# Receiver.net
KiCad netlist of a schematic drawn in EAGLE
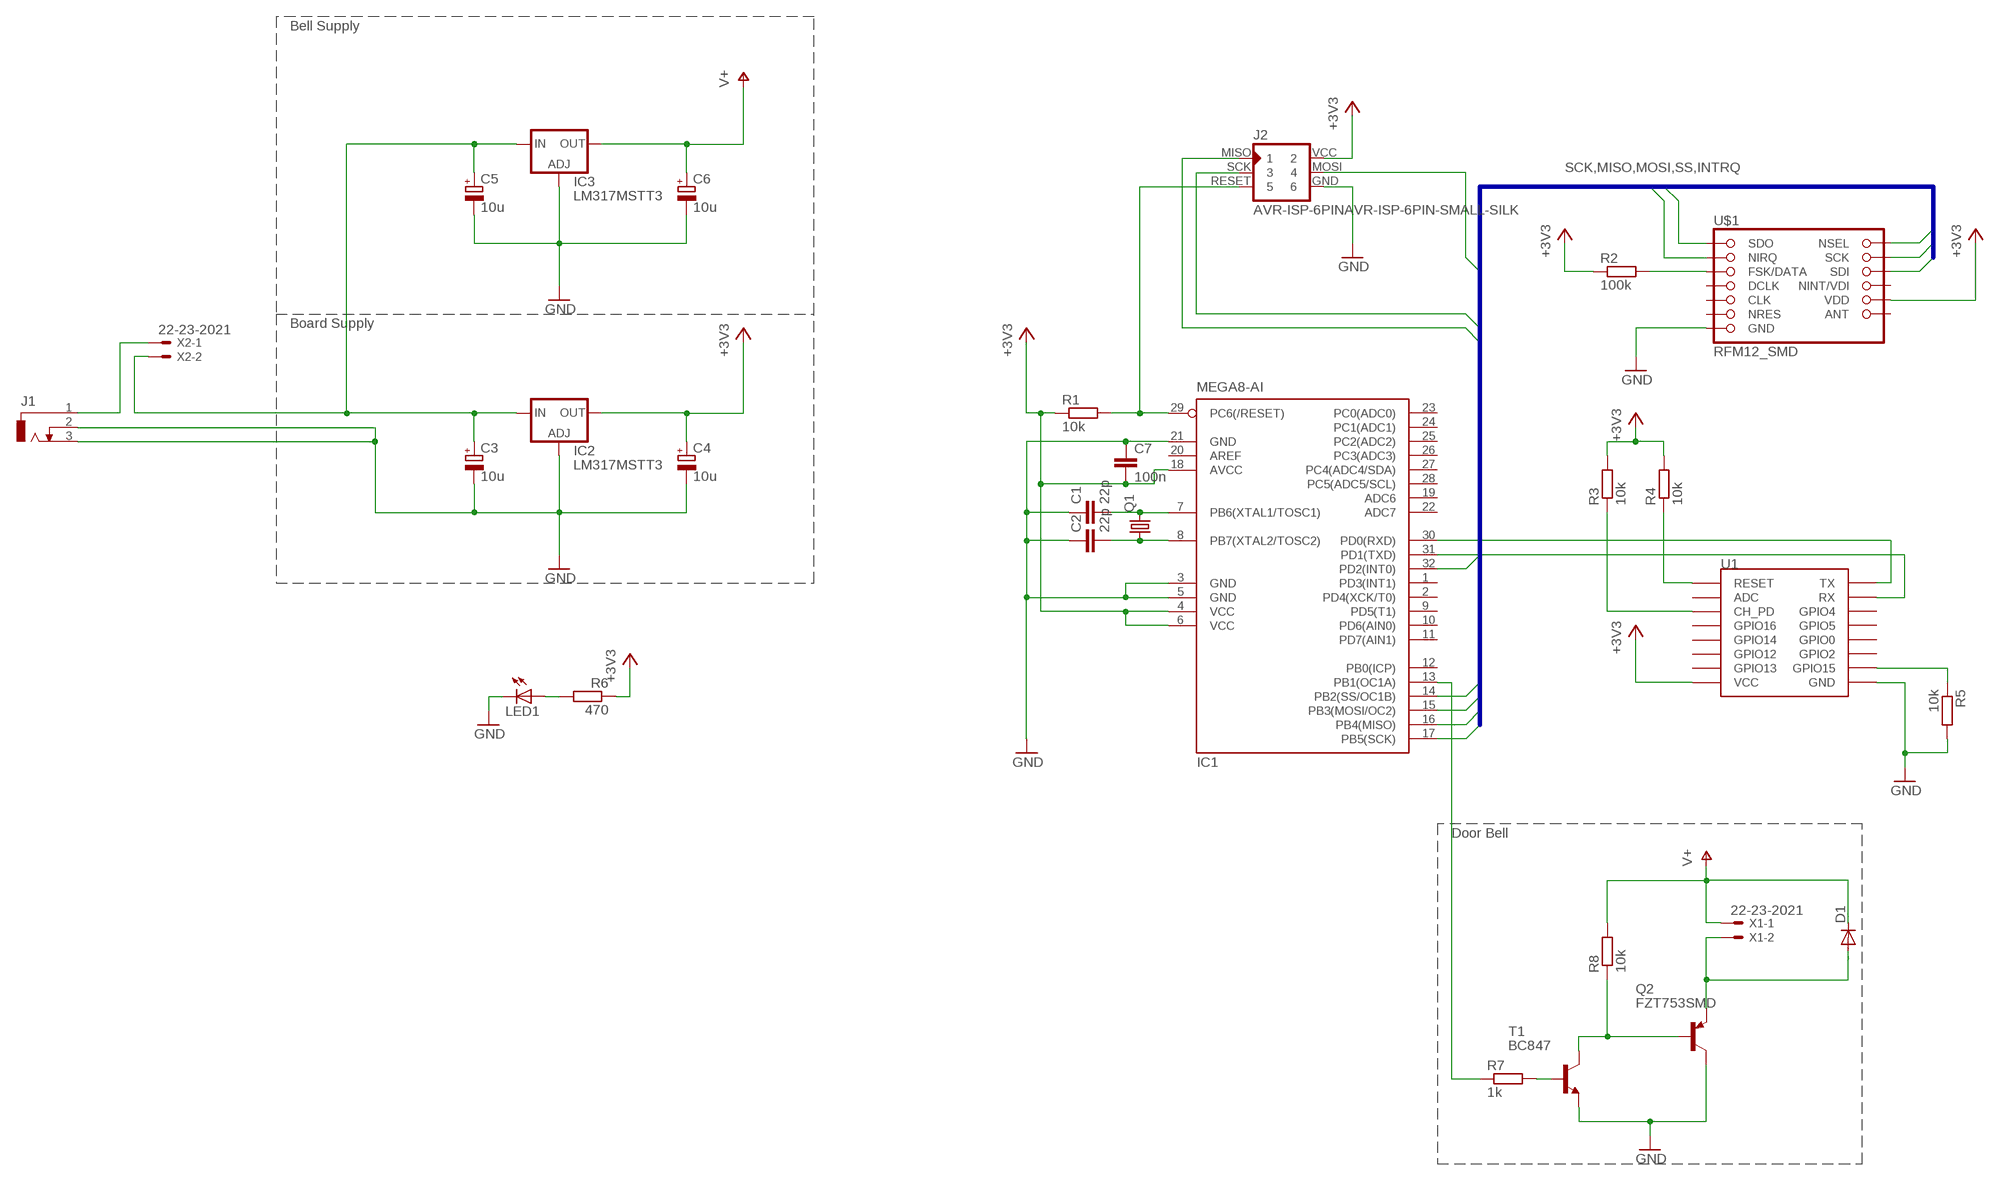
[diagram p0: schematic, sheet 1]

(export (version "E")
  (design (tool "Eeschema 10.0.6"))
  (components
    (comp (ref "C1")
      (value "22p")
      (footprint "eagle-import:C0603")
      (libsource (lib "eagle-import") (part "C-EUC0603"))
    )
    (comp (ref "C2")
      (value "22p")
      (footprint "eagle-import:C0603")
      (libsource (lib "eagle-import") (part "C-EUC0603"))
    )
    (comp (ref "C3")
      (value "10u")
      (footprint "eagle-import:E1,8-4")
      (libsource (lib "eagle-import") (part "CPOL-EUE1.8-4"))
    )
    (comp (ref "C4")
      (value "10u")
      (footprint "eagle-import:E1,8-4")
      (libsource (lib "eagle-import") (part "CPOL-EUE1.8-4"))
    )
    (comp (ref "C5")
      (value "10u")
      (footprint "eagle-import:E1,8-4")
      (libsource (lib "eagle-import") (part "CPOL-EUE1.8-4"))
    )
    (comp (ref "C6")
      (value "10u")
      (footprint "eagle-import:E1,8-4")
      (libsource (lib "eagle-import") (part "CPOL-EUE1.8-4"))
    )
    (comp (ref "C7")
      (value "100n")
      (footprint "eagle-import:C0603")
      (libsource (lib "eagle-import") (part "C-EUC0603"))
    )
    (comp (ref "D1")
      (value "DIODE-DO-214AC")
      (footprint "eagle-import:DO-214AC")
      (libsource (lib "eagle-import") (part "DIODE-DO-214AC"))
    )
    (comp (ref "IC1")
      (value "MEGA8-AI")
      (footprint "eagle-import:TQFP32-08")
      (fields (field (name "MPN") "ATMEGA8-16AU"))
      (libsource (lib "eagle-import") (part "MEGA8-AI"))
    )
    (comp (ref "IC2")
      (value "LM317MSTT3")
      (footprint "eagle-import:SOT223")
      (libsource (lib "eagle-import") (part "LM317?MSTT3"))
    )
    (comp (ref "IC3")
      (value "LM317MSTT3")
      (footprint "eagle-import:SOT223")
      (libsource (lib "eagle-import") (part "LM317?MSTT3"))
    )
    (comp (ref "J1")
      (value "DCJ0303")
      (footprint "eagle-import:DCJ0303")
      (libsource (lib "eagle-import") (part "DCJ0303"))
    )
    (comp (ref "J2")
      (value "AVR-ISP-6PINAVR-ISP-6PIN-SMALL-SILK")
      (footprint "eagle-import:AVR-ISP-6PIN-SMAILL-SILK")
      (libsource (lib "eagle-import") (part "AVR-ISP-6PINAVR-ISP-6PIN-SMALL-SILK"))
    )
    (comp (ref "LED1")
      (value "LED3MM")
      (footprint "eagle-import:LED3MM")
      (libsource (lib "eagle-import") (part "LED3MM"))
    )
    (comp (ref "Q1")
      (value "CRYSTALHC49S")
      (footprint "eagle-import:HC49_S")
      (libsource (lib "eagle-import") (part "CRYSTALHC49S"))
    )
    (comp (ref "Q2")
      (value "FZT753SMD")
      (footprint "eagle-import:SOT223")
      (libsource (lib "eagle-import") (part "FZT753SMD"))
    )
    (comp (ref "R1")
      (value "10k")
      (footprint "eagle-import:R0603")
      (libsource (lib "eagle-import") (part "R-EU_R0603"))
    )
    (comp (ref "R2")
      (value "100k")
      (footprint "eagle-import:R0603")
      (libsource (lib "eagle-import") (part "R-EU_R0603"))
    )
    (comp (ref "R3")
      (value "10k")
      (footprint "eagle-import:R0603")
      (libsource (lib "eagle-import") (part "R-EU_R0603"))
    )
    (comp (ref "R4")
      (value "10k")
      (footprint "eagle-import:R0603")
      (libsource (lib "eagle-import") (part "R-EU_R0603"))
    )
    (comp (ref "R5")
      (value "10k")
      (footprint "eagle-import:R0603")
      (libsource (lib "eagle-import") (part "R-EU_R0603"))
    )
    (comp (ref "R6")
      (value "470")
      (footprint "eagle-import:R0603")
      (libsource (lib "eagle-import") (part "R-EU_R0603"))
    )
    (comp (ref "R7")
      (value "1k")
      (footprint "eagle-import:R0603")
      (libsource (lib "eagle-import") (part "R-EU_R0603"))
    )
    (comp (ref "R8")
      (value "10k")
      (footprint "eagle-import:R0603")
      (libsource (lib "eagle-import") (part "R-EU_R0603"))
    )
    (comp (ref "T1")
      (value "BC847")
      (footprint "eagle-import:SOT23")
      (libsource (lib "eagle-import") (part "BC847"))
    )
    (comp (ref "U$1")
      (value "RFM12_SMD")
      (footprint "eagle-import:RFM12_SMD")
      (libsource (lib "eagle-import") (part "RFM12_SMD"))
    )
    (comp (ref "U1")
      (value "ESP12SMD")
      (footprint "eagle-import:ESP12-SMD")
      (libsource (lib "eagle-import") (part "ESP12SMD"))
    )
    (comp (ref "X1")
      (value "22-23-2021")
      (footprint "eagle-import:22-23-2021")
      (fields (field (name "MF") "MOLEX"))
      (libsource (lib "eagle-import") (part "22-23-2021"))
    )
    (comp (ref "X2")
      (value "22-23-2021")
      (footprint "eagle-import:22-23-2021")
      (fields (field (name "MF") "MOLEX"))
      (libsource (lib "eagle-import") (part "22-23-2021"))
    )
  )
  (nets
    (net (code "1") (name "+3V3") (class "Default")
      (node (ref "C4") (pin "+") (pinfunction "+_+") (pintype "passive"))
      (node (ref "C7") (pin "2") (pinfunction "2_2") (pintype "passive"))
      (node (ref "IC1") (pin "18") (pinfunction "AVCC_18") (pintype "power_in"))
      (node (ref "IC1") (pin "4") (pinfunction "VCC_4") (pintype "power_in"))
      (node (ref "IC1") (pin "6") (pinfunction "VCC_6") (pintype "power_in"))
      (node (ref "IC2") (pin "4") (pinfunction "OUT_4") (pintype "passive"))
      (node (ref "J2") (pin "VCC") (pinfunction "2_VCC") (pintype "passive"))
      (node (ref "R1") (pin "1") (pinfunction "1_1") (pintype "passive"))
      (node (ref "R2") (pin "1") (pinfunction "1_1") (pintype "passive"))
      (node (ref "R3") (pin "2") (pinfunction "2_2") (pintype "passive"))
      (node (ref "R4") (pin "2") (pinfunction "2_2") (pintype "passive"))
      (node (ref "R6") (pin "1") (pinfunction "1_1") (pintype "passive"))
      (node (ref "U$1") (pin "9") (pinfunction "VDD_9") (pintype "power_in"))
      (node (ref "U1") (pin "VCC") (pinfunction "VCC_VCC") (pintype "bidirectional"))
    )
    (net (code "2") (name "/INTRQ") (class "Default")
      (node (ref "IC1") (pin "32") (pinfunction "PD2(INT0)_32") (pintype "bidirectional"))
      (node (ref "U$1") (pin "2") (pinfunction "NIRQ_2") (pintype "output"))
    )
    (net (code "3") (name "/MISO") (class "Default")
      (node (ref "IC1") (pin "16") (pinfunction "PB4(MISO)_16") (pintype "bidirectional"))
      (node (ref "J2") (pin "MISO") (pinfunction "1_MISO") (pintype "passive"))
      (node (ref "U$1") (pin "1") (pinfunction "SDO_1") (pintype "output"))
    )
    (net (code "4") (name "/MOSI") (class "Default")
      (node (ref "IC1") (pin "15") (pinfunction "PB3(MOSI/OC2)_15") (pintype "bidirectional"))
      (node (ref "J2") (pin "MOSI") (pinfunction "4_MOSI") (pintype "passive"))
      (node (ref "U$1") (pin "12") (pinfunction "SDI_12") (pintype "input"))
    )
    (net (code "5") (name "/SCK") (class "Default")
      (node (ref "IC1") (pin "17") (pinfunction "PB5(SCK)_17") (pintype "bidirectional"))
      (node (ref "J2") (pin "SCK") (pinfunction "3_SCK") (pintype "passive"))
      (node (ref "U$1") (pin "13") (pinfunction "SCK_13") (pintype "input"))
    )
    (net (code "6") (name "/SS") (class "Default")
      (node (ref "IC1") (pin "14") (pinfunction "PB2(SS/OC1B)_14") (pintype "bidirectional"))
      (node (ref "U$1") (pin "14") (pinfunction "NSEL_14") (pintype "input"))
    )
    (net (code "8") (name "GND") (class "Default")
      (node (ref "C1") (pin "1") (pinfunction "1_1") (pintype "passive"))
      (node (ref "C2") (pin "1") (pinfunction "1_1") (pintype "passive"))
      (node (ref "C3") (pin "-") (pinfunction "-_-") (pintype "passive"))
      (node (ref "C4") (pin "-") (pinfunction "-_-") (pintype "passive"))
      (node (ref "C5") (pin "-") (pinfunction "-_-") (pintype "passive"))
      (node (ref "C6") (pin "-") (pinfunction "-_-") (pintype "passive"))
      (node (ref "C7") (pin "1") (pinfunction "1_1") (pintype "passive"))
      (node (ref "IC1") (pin "21") (pinfunction "GND_21") (pintype "power_in"))
      (node (ref "IC1") (pin "3") (pinfunction "GND_3") (pintype "power_in"))
      (node (ref "IC1") (pin "5") (pinfunction "GND_5") (pintype "power_in"))
      (node (ref "IC2") (pin "1") (pinfunction "ADJ_1") (pintype "input"))
      (node (ref "IC3") (pin "1") (pinfunction "ADJ_1") (pintype "input"))
      (node (ref "J1") (pin "2") (pinfunction "2_2") (pintype "passive"))
      (node (ref "J1") (pin "3") (pinfunction "3_3") (pintype "passive"))
      (node (ref "J2") (pin "GND") (pinfunction "6_GND") (pintype "passive"))
      (node (ref "LED1") (pin "K") (pinfunction "C_K") (pintype "passive"))
      (node (ref "Q2") (pin "2") (pinfunction "C_2") (pintype "passive"))
      (node (ref "Q2") (pin "4") (pinfunction "C_4") (pintype "passive"))
      (node (ref "R5") (pin "2") (pinfunction "2_2") (pintype "passive"))
      (node (ref "T1") (pin "2") (pinfunction "E_2") (pintype "passive"))
      (node (ref "U$1") (pin "10") (pinfunction "GND_10") (pintype "power_in"))
      (node (ref "U$1") (pin "7") (pinfunction "GND_7") (pintype "power_in"))
      (node (ref "U1") (pin "GND") (pinfunction "GND_GND") (pintype "bidirectional"))
    )
    (net (code "9") (name "Net-(IC1-PB1(OC1A))") (class "Default")
      (node (ref "IC1") (pin "13") (pinfunction "PB1(OC1A)_13") (pintype "bidirectional"))
      (node (ref "R7") (pin "1") (pinfunction "1_1") (pintype "passive"))
    )
    (net (code "10") (name "Net-(IC1-PB6(XTAL1{slash}TOSC1))") (class "Default")
      (node (ref "C1") (pin "2") (pinfunction "2_2") (pintype "passive"))
      (node (ref "IC1") (pin "7") (pinfunction "PB6(XTAL1/TOSC1)_7") (pintype "bidirectional"))
      (node (ref "Q1") (pin "2") (pinfunction "2_2") (pintype "passive"))
    )
    (net (code "11") (name "Net-(IC1-PB7(XTAL2{slash}TOSC2))") (class "Default")
      (node (ref "C2") (pin "2") (pinfunction "2_2") (pintype "passive"))
      (node (ref "IC1") (pin "8") (pinfunction "PB7(XTAL2/TOSC2)_8") (pintype "bidirectional"))
      (node (ref "Q1") (pin "1") (pinfunction "1_1") (pintype "passive"))
    )
    (net (code "12") (name "Net-(IC1-PC6({slash}RESET))") (class "Default")
      (node (ref "IC1") (pin "29") (pinfunction "PC6(/RESET)_29") (pintype "bidirectional"))
      (node (ref "J2") (pin "RESET") (pinfunction "5_RESET") (pintype "passive"))
      (node (ref "R1") (pin "2") (pinfunction "2_2") (pintype "passive"))
    )
    (net (code "13") (name "Net-(IC1-PD0(RXD))") (class "Default")
      (node (ref "IC1") (pin "30") (pinfunction "PD0(RXD)_30") (pintype "bidirectional"))
      (node (ref "U1") (pin "TXD0") (pinfunction "TX_TXD0") (pintype "bidirectional"))
    )
    (net (code "14") (name "Net-(IC1-PD1(TXD))") (class "Default")
      (node (ref "IC1") (pin "31") (pinfunction "PD1(TXD)_31") (pintype "bidirectional"))
      (node (ref "U1") (pin "RXD0") (pinfunction "RX_RXD0") (pintype "bidirectional"))
    )
    (net (code "15") (name "Net-(IC2-IN)") (class "Default")
      (node (ref "C3") (pin "+") (pinfunction "+_+") (pintype "passive"))
      (node (ref "C5") (pin "+") (pinfunction "+_+") (pintype "passive"))
      (node (ref "IC2") (pin "3") (pinfunction "IN_3") (pintype "input"))
      (node (ref "IC3") (pin "3") (pinfunction "IN_3") (pintype "input"))
      (node (ref "X2") (pin "2") (pinfunction "S_2") (pintype "passive"))
    )
    (net (code "16") (name "Net-(LED1-PadA)") (class "Default")
      (node (ref "LED1") (pin "A") (pinfunction "A_A") (pintype "passive"))
      (node (ref "R6") (pin "2") (pinfunction "2_2") (pintype "passive"))
    )
    (net (code "17") (name "Net-(Q2-B)") (class "Default")
      (node (ref "Q2") (pin "1") (pinfunction "B_1") (pintype "passive"))
      (node (ref "R8") (pin "1") (pinfunction "1_1") (pintype "passive"))
      (node (ref "T1") (pin "3") (pinfunction "C_3") (pintype "passive"))
    )
    (net (code "18") (name "Net-(Q2-E)") (class "Default")
      (node (ref "D1") (pin "A") (pinfunction "A_A") (pintype "passive"))
      (node (ref "Q2") (pin "3") (pinfunction "E_3") (pintype "passive"))
      (node (ref "X1") (pin "2") (pinfunction "S_2") (pintype "passive"))
    )
    (net (code "19") (name "Net-(R3-Pad1)") (class "Default")
      (node (ref "R3") (pin "1") (pinfunction "1_1") (pintype "passive"))
      (node (ref "U1") (pin "CH_PD") (pinfunction "CH_PD_CH_PD") (pintype "bidirectional"))
    )
    (net (code "20") (name "Net-(R4-Pad1)") (class "Default")
      (node (ref "R4") (pin "1") (pinfunction "1_1") (pintype "passive"))
      (node (ref "U1") (pin "RESET") (pinfunction "RESET_RESET") (pintype "bidirectional"))
    )
    (net (code "21") (name "Net-(R5-Pad1)") (class "Default")
      (node (ref "R5") (pin "1") (pinfunction "1_1") (pintype "passive"))
      (node (ref "U1") (pin "GPIO15") (pinfunction "GPIO15_GPIO15") (pintype "bidirectional"))
    )
    (net (code "22") (name "Net-(T1-B)") (class "Default")
      (node (ref "R7") (pin "2") (pinfunction "2_2") (pintype "passive"))
      (node (ref "T1") (pin "1") (pinfunction "B_1") (pintype "passive"))
    )
    (net (code "23") (name "Net-(U$1-FSK{slash}DATA)") (class "Default")
      (node (ref "R2") (pin "2") (pinfunction "2_2") (pintype "passive"))
      (node (ref "U$1") (pin "3") (pinfunction "FSK/DATA_3") (pintype "bidirectional"))
    )
    (net (code "24") (name "Net-(X2A-S)") (class "Default")
      (node (ref "J1") (pin "1") (pinfunction "1_1") (pintype "passive"))
      (node (ref "X2") (pin "1") (pinfunction "S_1") (pintype "passive"))
    )
    (net (code "25") (name "V+") (class "Default")
      (node (ref "C6") (pin "+") (pinfunction "+_+") (pintype "passive"))
      (node (ref "D1") (pin "C") (pinfunction "C_C") (pintype "passive"))
      (node (ref "IC3") (pin "4") (pinfunction "OUT_4") (pintype "passive"))
      (node (ref "R8") (pin "2") (pinfunction "2_2") (pintype "passive"))
      (node (ref "X1") (pin "1") (pinfunction "S_1") (pintype "passive"))
    )
    (net (code "26") (name "unconnected-(IC1-ADC6-Pad19)") (class "Default")
      (node (ref "IC1") (pin "19") (pinfunction "ADC6_19") (pintype "bidirectional"))
    )
    (net (code "27") (name "unconnected-(IC1-ADC7-Pad22)") (class "Default")
      (node (ref "IC1") (pin "22") (pinfunction "ADC7_22") (pintype "bidirectional"))
    )
    (net (code "28") (name "unconnected-(IC1-AREF-Pad20)") (class "Default")
      (node (ref "IC1") (pin "20") (pinfunction "AREF_20") (pintype "passive"))
    )
    (net (code "29") (name "unconnected-(IC1-PB0(ICP)-Pad12)") (class "Default")
      (node (ref "IC1") (pin "12") (pinfunction "PB0(ICP)_12") (pintype "bidirectional"))
    )
    (net (code "30") (name "unconnected-(IC1-PC0(ADC0)-Pad23)") (class "Default")
      (node (ref "IC1") (pin "23") (pinfunction "PC0(ADC0)_23") (pintype "bidirectional"))
    )
    (net (code "31") (name "unconnected-(IC1-PC1(ADC1)-Pad24)") (class "Default")
      (node (ref "IC1") (pin "24") (pinfunction "PC1(ADC1)_24") (pintype "bidirectional"))
    )
    (net (code "32") (name "unconnected-(IC1-PC2(ADC2)-Pad25)") (class "Default")
      (node (ref "IC1") (pin "25") (pinfunction "PC2(ADC2)_25") (pintype "bidirectional"))
    )
    (net (code "33") (name "unconnected-(IC1-PC3(ADC3)-Pad26)") (class "Default")
      (node (ref "IC1") (pin "26") (pinfunction "PC3(ADC3)_26") (pintype "bidirectional"))
    )
    (net (code "34") (name "unconnected-(IC1-PC4(ADC4{slash}SDA)-Pad27)") (class "Default")
      (node (ref "IC1") (pin "27") (pinfunction "PC4(ADC4/SDA)_27") (pintype "bidirectional"))
    )
    (net (code "35") (name "unconnected-(IC1-PC5(ADC5{slash}SCL)-Pad28)") (class "Default")
      (node (ref "IC1") (pin "28") (pinfunction "PC5(ADC5/SCL)_28") (pintype "bidirectional"))
    )
    (net (code "36") (name "unconnected-(IC1-PD3(INT1)-Pad1)") (class "Default")
      (node (ref "IC1") (pin "1") (pinfunction "PD3(INT1)_1") (pintype "bidirectional"))
    )
    (net (code "37") (name "unconnected-(IC1-PD4(XCK{slash}T0)-Pad2)") (class "Default")
      (node (ref "IC1") (pin "2") (pinfunction "PD4(XCK/T0)_2") (pintype "bidirectional"))
    )
    (net (code "38") (name "unconnected-(IC1-PD5(T1)-Pad9)") (class "Default")
      (node (ref "IC1") (pin "9") (pinfunction "PD5(T1)_9") (pintype "bidirectional"))
    )
    (net (code "39") (name "unconnected-(IC1-PD6(AIN0)-Pad10)") (class "Default")
      (node (ref "IC1") (pin "10") (pinfunction "PD6(AIN0)_10") (pintype "bidirectional"))
    )
    (net (code "40") (name "unconnected-(IC1-PD7(AIN1)-Pad11)") (class "Default")
      (node (ref "IC1") (pin "11") (pinfunction "PD7(AIN1)_11") (pintype "bidirectional"))
    )
    (net (code "41") (name "unconnected-(U$1-ANT-Pad8)") (class "Default")
      (node (ref "U$1") (pin "8") (pinfunction "ANT_8") (pintype "output"))
    )
    (net (code "42") (name "unconnected-(U$1-CLK-Pad5)") (class "Default")
      (node (ref "U$1") (pin "5") (pinfunction "CLK_5") (pintype "output"))
    )
    (net (code "43") (name "unconnected-(U$1-DCLK-Pad4)") (class "Default")
      (node (ref "U$1") (pin "4") (pinfunction "DCLK_4") (pintype "bidirectional"))
    )
    (net (code "44") (name "unconnected-(U$1-NINT{slash}VDI-Pad11)") (class "Default")
      (node (ref "U$1") (pin "11") (pinfunction "NINT/VDI_11") (pintype "bidirectional"))
    )
    (net (code "45") (name "unconnected-(U$1-NRES-Pad6)") (class "Default")
      (node (ref "U$1") (pin "6") (pinfunction "NRES_6") (pintype "bidirectional"))
    )
    (net (code "46") (name "unconnected-(U1-PadADC)") (class "Default")
      (node (ref "U1") (pin "ADC") (pinfunction "ADC_ADC") (pintype "bidirectional"))
    )
    (net (code "47") (name "unconnected-(U1-PadGPIO0)") (class "Default")
      (node (ref "U1") (pin "GPIO0") (pinfunction "GPIO0_GPIO0") (pintype "bidirectional"))
    )
    (net (code "48") (name "unconnected-(U1-PadGPIO2)") (class "Default")
      (node (ref "U1") (pin "GPIO2") (pinfunction "GPIO2_GPIO2") (pintype "bidirectional"))
    )
    (net (code "49") (name "unconnected-(U1-PadGPIO4)") (class "Default")
      (node (ref "U1") (pin "GPIO4") (pinfunction "GPIO4_GPIO4") (pintype "bidirectional"))
    )
    (net (code "50") (name "unconnected-(U1-PadGPIO5)") (class "Default")
      (node (ref "U1") (pin "GPIO5") (pinfunction "GPIO5_GPIO5") (pintype "bidirectional"))
    )
    (net (code "51") (name "unconnected-(U1-PadGPIO12)") (class "Default")
      (node (ref "U1") (pin "GPIO12") (pinfunction "GPIO12_GPIO12") (pintype "bidirectional"))
    )
    (net (code "52") (name "unconnected-(U1-PadGPIO13)") (class "Default")
      (node (ref "U1") (pin "GPIO13") (pinfunction "GPIO13_GPIO13") (pintype "bidirectional"))
    )
    (net (code "53") (name "unconnected-(U1-PadGPIO14)") (class "Default")
      (node (ref "U1") (pin "GPIO14") (pinfunction "GPIO14_GPIO14") (pintype "bidirectional"))
    )
    (net (code "54") (name "unconnected-(U1-PadGPIO16)") (class "Default")
      (node (ref "U1") (pin "GPIO16") (pinfunction "GPIO16_GPIO16") (pintype "bidirectional"))
    )
  )
)
